# akabeacon_square_type3_MDBT40.net
KiCad netlist of a schematic drawn in EAGLE
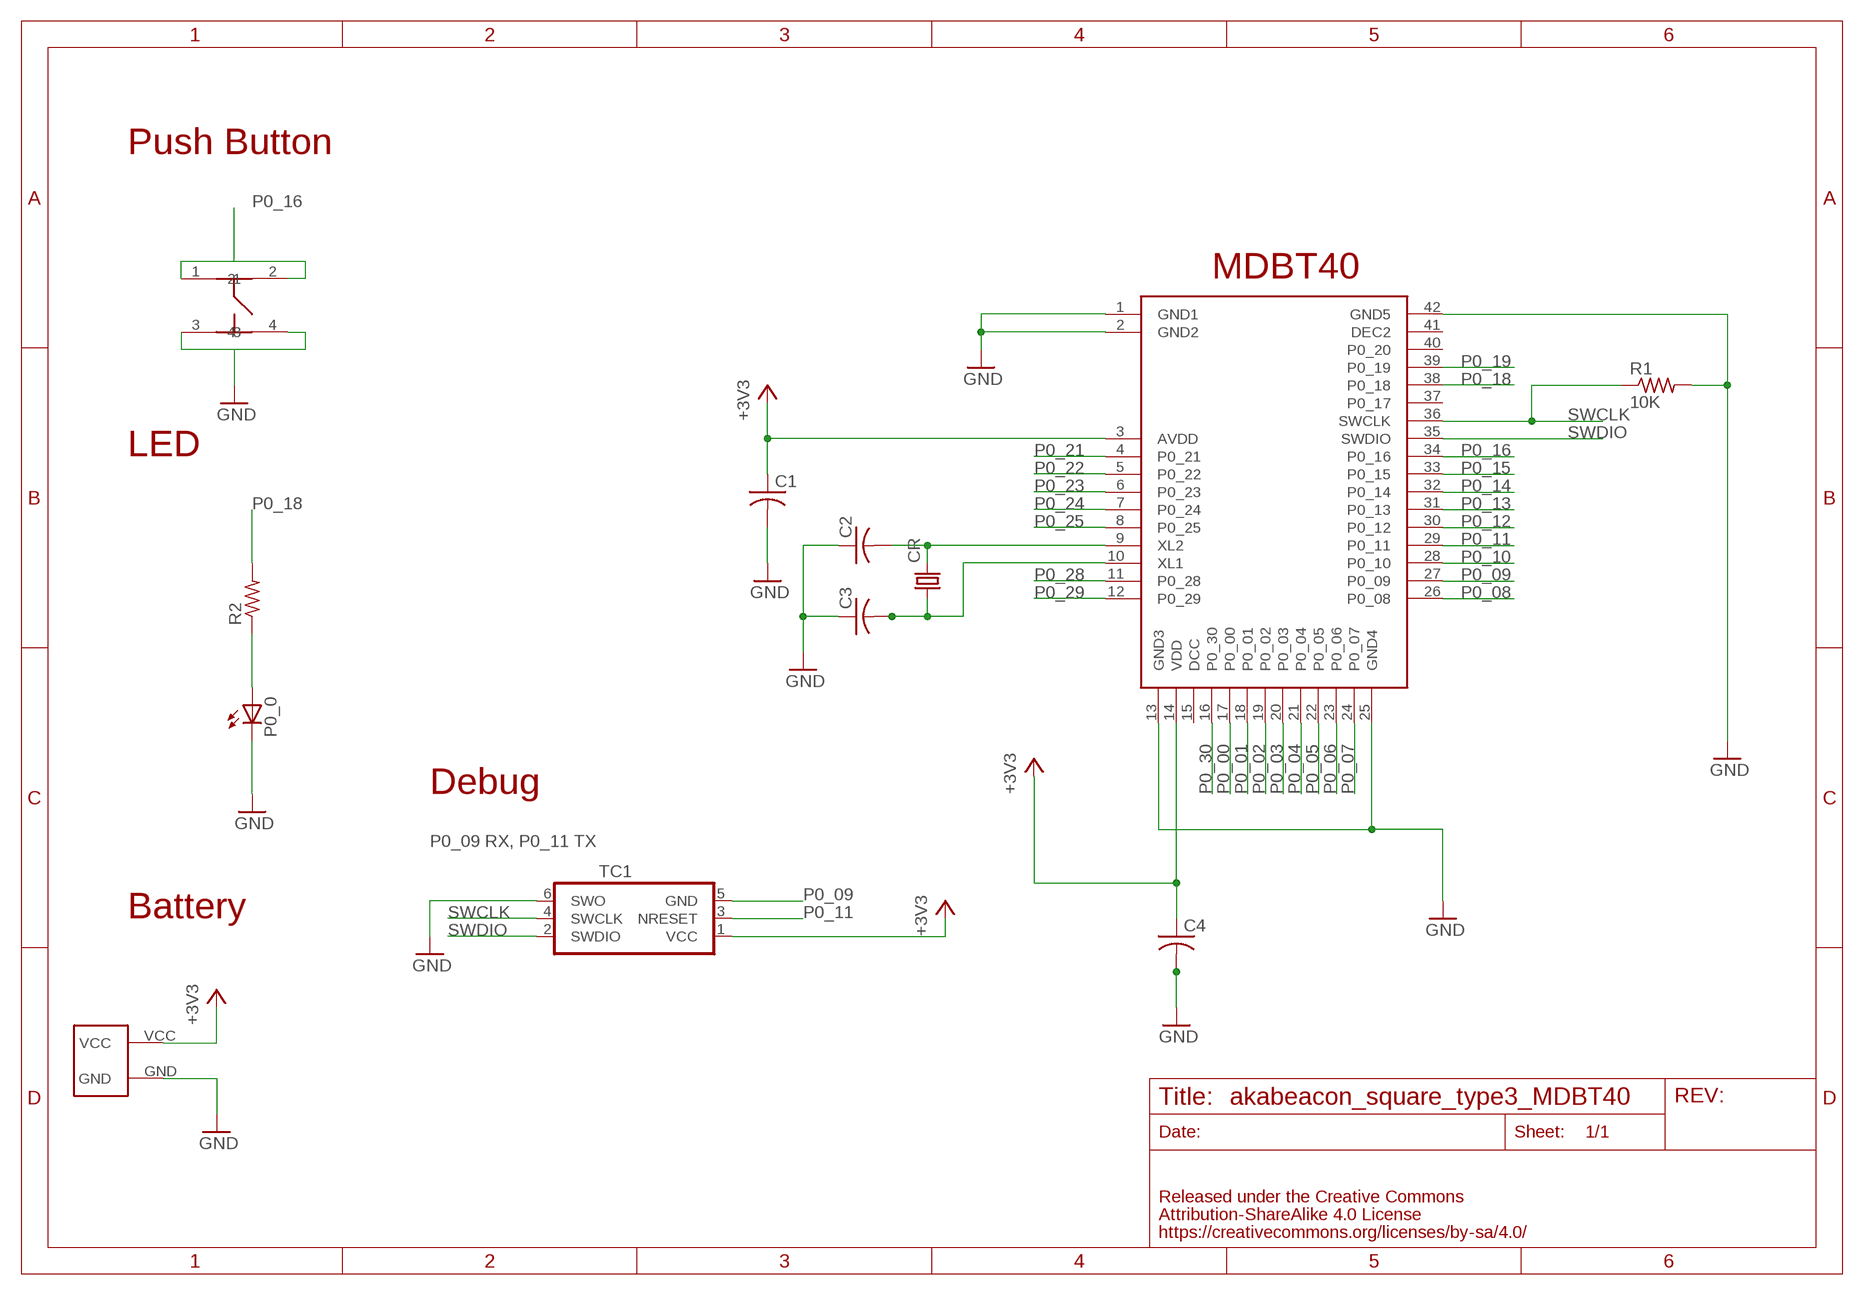
[diagram p0: schematic, sheet 1]

(export (version "E")
  (design (tool "Eeschema 10.0.6"))
  (components
    (comp (ref "C1")
      (value "C-USC0603")
      (footprint "eagle-import:C0603")
      (libsource (lib "eagle-import") (part "C-USC0603"))
    )
    (comp (ref "C2")
      (value "C-USC0603")
      (footprint "eagle-import:C0603")
      (libsource (lib "eagle-import") (part "C-USC0603"))
    )
    (comp (ref "C3")
      (value "C-USC0603")
      (footprint "eagle-import:C0603")
      (libsource (lib "eagle-import") (part "C-USC0603"))
    )
    (comp (ref "C4")
      (value "C-USC0603")
      (footprint "eagle-import:C0603")
      (libsource (lib "eagle-import") (part "C-USC0603"))
    )
    (comp (ref "CR")
      (value "FC-12M")
      (footprint "eagle-import:FC-12M")
      (libsource (lib "eagle-import") (part "FC-12M"))
    )
    (comp (ref "P0_0")
      (value "LEDCHIP-LED0603")
      (footprint "eagle-import:CHIP-LED0603")
      (libsource (lib "eagle-import") (part "LEDCHIP-LED0603"))
    )
    (comp (ref "R1")
      (value "10K")
      (footprint "eagle-import:R0603")
      (libsource (lib "eagle-import") (part "R-US_R0603"))
    )
    (comp (ref "R2")
      (value "R-US_R0603")
      (footprint "eagle-import:R0603")
      (libsource (lib "eagle-import") (part "R-US_R0603"))
    )
    (comp (ref "TC1")
      (value "TC2030-IDC-NL")
      (footprint "eagle-import:TC2030-IDC-NL")
      (libsource (lib "eagle-import") (part "TC2030-IDC-NL"))
    )
    (comp (ref "U$2")
      (value "SQUARE-TYPE2-TC2030")
      (footprint "eagle-import:SQUARE-TYPE2-TC2030")
      (libsource (lib "eagle-import") (part "SQUARE-TYPE2-TC2030"))
    )
    (comp (ref "U$3")
      (value "RAYTAC-MDBT40")
      (footprint "eagle-import:RAYTAC-MDBT40")
      (libsource (lib "eagle-import") (part "RAYTAC-MDBT40"))
    )
    (comp (ref "U$6")
      (value "SWICTH-4P(KMR2)")
      (footprint "eagle-import:SWITCH-4P(KMR2)")
      (libsource (lib "eagle-import") (part "SWICTH-4P(KMR2)"))
    )
  )
  (nets
    (net (code "1") (name "+3V3") (class "Default")
      (node (ref "C1") (pin "1") (pinfunction "1_1") (pintype "passive"))
      (node (ref "C4") (pin "1") (pinfunction "1_1") (pintype "passive"))
      (node (ref "TC1") (pin "1") (pinfunction "VCC_1") (pintype "passive"))
      (node (ref "U$2") (pin "VCC") (pinfunction "VCC_VCC") (pintype "bidirectional"))
      (node (ref "U$3") (pin "14") (pinfunction "VDD_14") (pintype "bidirectional"))
      (node (ref "U$3") (pin "3") (pinfunction "AVDD_3") (pintype "bidirectional"))
    )
    (net (code "2") (name "/P0_00") (class "Default")
      (node (ref "U$3") (pin "17") (pinfunction "P0_00_17") (pintype "bidirectional"))
    )
    (net (code "3") (name "/P0_01") (class "Default")
      (node (ref "U$3") (pin "18") (pinfunction "P0_01_18") (pintype "bidirectional"))
    )
    (net (code "4") (name "/P0_02") (class "Default")
      (node (ref "U$3") (pin "19") (pinfunction "P0_02_19") (pintype "bidirectional"))
    )
    (net (code "5") (name "/P0_03") (class "Default")
      (node (ref "U$3") (pin "20") (pinfunction "P0_03_20") (pintype "bidirectional"))
    )
    (net (code "6") (name "/P0_04") (class "Default")
      (node (ref "U$3") (pin "21") (pinfunction "P0_04_21") (pintype "bidirectional"))
    )
    (net (code "7") (name "/P0_05") (class "Default")
      (node (ref "U$3") (pin "22") (pinfunction "P0_05_22") (pintype "bidirectional"))
    )
    (net (code "8") (name "/P0_06") (class "Default")
      (node (ref "U$3") (pin "23") (pinfunction "P0_06_23") (pintype "bidirectional"))
    )
    (net (code "9") (name "/P0_07") (class "Default")
      (node (ref "U$3") (pin "24") (pinfunction "P0_07_24") (pintype "bidirectional"))
    )
    (net (code "10") (name "/P0_08") (class "Default")
      (node (ref "U$3") (pin "26") (pinfunction "P0_08_26") (pintype "bidirectional"))
    )
    (net (code "11") (name "/P0_09") (class "Default")
      (node (ref "TC1") (pin "5") (pinfunction "GND_5") (pintype "passive"))
      (node (ref "U$3") (pin "27") (pinfunction "P0_09_27") (pintype "bidirectional"))
    )
    (net (code "12") (name "/P0_10") (class "Default")
      (node (ref "U$3") (pin "28") (pinfunction "P0_10_28") (pintype "bidirectional"))
    )
    (net (code "13") (name "/P0_11") (class "Default")
      (node (ref "TC1") (pin "3") (pinfunction "NRESET_3") (pintype "passive"))
      (node (ref "U$3") (pin "29") (pinfunction "P0_11_29") (pintype "bidirectional"))
    )
    (net (code "14") (name "/P0_12") (class "Default")
      (node (ref "U$3") (pin "30") (pinfunction "P0_12_30") (pintype "bidirectional"))
    )
    (net (code "15") (name "/P0_13") (class "Default")
      (node (ref "U$3") (pin "31") (pinfunction "P0_13_31") (pintype "bidirectional"))
    )
    (net (code "16") (name "/P0_14") (class "Default")
      (node (ref "U$3") (pin "32") (pinfunction "P0_14_32") (pintype "bidirectional"))
    )
    (net (code "17") (name "/P0_15") (class "Default")
      (node (ref "U$3") (pin "33") (pinfunction "P0_15_33") (pintype "bidirectional"))
    )
    (net (code "18") (name "/P0_16") (class "Default")
      (node (ref "U$3") (pin "34") (pinfunction "P0_16_34") (pintype "bidirectional"))
      (node (ref "U$6") (pin "1") (pinfunction "1_1") (pintype "bidirectional"))
      (node (ref "U$6") (pin "2") (pinfunction "2_2") (pintype "bidirectional"))
    )
    (net (code "19") (name "/P0_18") (class "Default")
      (node (ref "R2") (pin "2") (pinfunction "2_2") (pintype "passive"))
      (node (ref "U$3") (pin "38") (pinfunction "P0_18_38") (pintype "bidirectional"))
    )
    (net (code "20") (name "/P0_19") (class "Default")
      (node (ref "U$3") (pin "39") (pinfunction "P0_19_39") (pintype "bidirectional"))
    )
    (net (code "21") (name "/P0_21") (class "Default")
      (node (ref "U$3") (pin "4") (pinfunction "P0_21_4") (pintype "bidirectional"))
    )
    (net (code "22") (name "/P0_22") (class "Default")
      (node (ref "U$3") (pin "5") (pinfunction "P0_22_5") (pintype "bidirectional"))
    )
    (net (code "23") (name "/P0_23") (class "Default")
      (node (ref "U$3") (pin "6") (pinfunction "P0_23_6") (pintype "bidirectional"))
    )
    (net (code "24") (name "/P0_24") (class "Default")
      (node (ref "U$3") (pin "7") (pinfunction "P0_24_7") (pintype "bidirectional"))
    )
    (net (code "25") (name "/P0_25") (class "Default")
      (node (ref "U$3") (pin "8") (pinfunction "P0_25_8") (pintype "bidirectional"))
    )
    (net (code "26") (name "/P0_28") (class "Default")
      (node (ref "U$3") (pin "11") (pinfunction "P0_28_11") (pintype "bidirectional"))
    )
    (net (code "27") (name "/P0_29") (class "Default")
      (node (ref "U$3") (pin "12") (pinfunction "P0_29_12") (pintype "bidirectional"))
    )
    (net (code "28") (name "/P0_30") (class "Default")
      (node (ref "U$3") (pin "16") (pinfunction "P0_30_16") (pintype "bidirectional"))
    )
    (net (code "29") (name "/SWCLK") (class "Default")
      (node (ref "R1") (pin "1") (pinfunction "1_1") (pintype "passive"))
      (node (ref "TC1") (pin "4") (pinfunction "SWCLK_4") (pintype "passive"))
      (node (ref "U$3") (pin "36") (pinfunction "SWCLK_36") (pintype "bidirectional"))
    )
    (net (code "30") (name "/SWDIO") (class "Default")
      (node (ref "TC1") (pin "2") (pinfunction "SWDIO_2") (pintype "passive"))
      (node (ref "U$3") (pin "35") (pinfunction "SWDIO_35") (pintype "bidirectional"))
    )
    (net (code "31") (name "GND") (class "Default")
      (node (ref "C1") (pin "2") (pinfunction "2_2") (pintype "passive"))
      (node (ref "C2") (pin "1") (pinfunction "1_1") (pintype "passive"))
      (node (ref "C3") (pin "1") (pinfunction "1_1") (pintype "passive"))
      (node (ref "C4") (pin "2") (pinfunction "2_2") (pintype "passive"))
      (node (ref "P0_0") (pin "C") (pinfunction "C_C") (pintype "passive"))
      (node (ref "R1") (pin "2") (pinfunction "2_2") (pintype "passive"))
      (node (ref "TC1") (pin "6") (pinfunction "SWO_6") (pintype "passive"))
      (node (ref "U$2") (pin "GND") (pinfunction "GND_GND") (pintype "bidirectional"))
      (node (ref "U$3") (pin "1") (pinfunction "GND1_1") (pintype "bidirectional"))
      (node (ref "U$3") (pin "13") (pinfunction "GND3_13") (pintype "bidirectional"))
      (node (ref "U$3") (pin "2") (pinfunction "GND2_2") (pintype "bidirectional"))
      (node (ref "U$3") (pin "25") (pinfunction "GND4_25") (pintype "bidirectional"))
      (node (ref "U$3") (pin "42") (pinfunction "GND5_42") (pintype "bidirectional"))
      (node (ref "U$6") (pin "3") (pinfunction "3_3") (pintype "bidirectional"))
      (node (ref "U$6") (pin "4") (pinfunction "4_4") (pintype "bidirectional"))
    )
    (net (code "32") (name "Net-(P0_0-PadA)") (class "Default")
      (node (ref "P0_0") (pin "A") (pinfunction "A_A") (pintype "passive"))
      (node (ref "R2") (pin "1") (pinfunction "1_1") (pintype "passive"))
    )
    (net (code "33") (name "Net-(U$3-XL1)") (class "Default")
      (node (ref "C3") (pin "2") (pinfunction "2_2") (pintype "passive"))
      (node (ref "CR") (pin "1") (pinfunction "1_1") (pintype "passive"))
      (node (ref "U$3") (pin "10") (pinfunction "XL1_10") (pintype "bidirectional"))
    )
    (net (code "34") (name "Net-(U$3-XL2)") (class "Default")
      (node (ref "C2") (pin "2") (pinfunction "2_2") (pintype "passive"))
      (node (ref "CR") (pin "2") (pinfunction "2_2") (pintype "passive"))
      (node (ref "U$3") (pin "9") (pinfunction "XL2_9") (pintype "bidirectional"))
    )
    (net (code "35") (name "unconnected-(U$3-DCC-Pad15)") (class "Default")
      (node (ref "U$3") (pin "15") (pinfunction "DCC_15") (pintype "bidirectional"))
    )
    (net (code "36") (name "unconnected-(U$3-DEC2-Pad41)") (class "Default")
      (node (ref "U$3") (pin "41") (pinfunction "DEC2_41") (pintype "bidirectional"))
    )
    (net (code "37") (name "unconnected-(U$3-P0_17-Pad37)") (class "Default")
      (node (ref "U$3") (pin "37") (pinfunction "P0_17_37") (pintype "bidirectional"))
    )
    (net (code "38") (name "unconnected-(U$3-P0_20-Pad40)") (class "Default")
      (node (ref "U$3") (pin "40") (pinfunction "P0_20_40") (pintype "bidirectional"))
    )
  )
)
